# TOP.net
KiCad netlist of a schematic drawn in Altium Designer
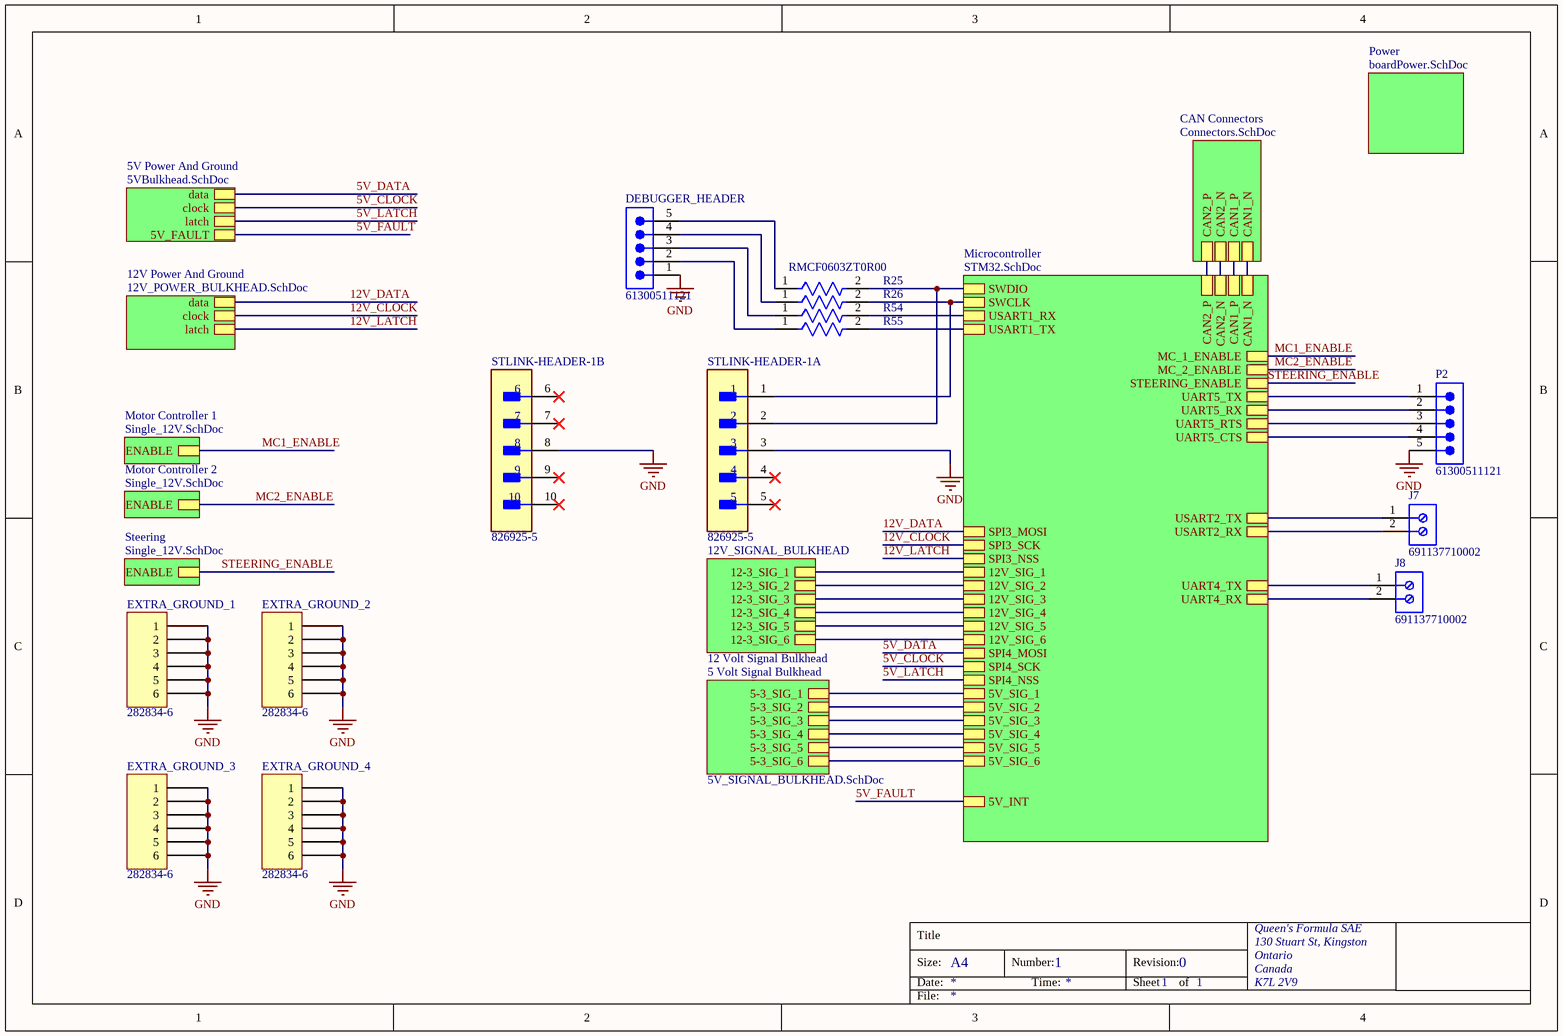
[diagram p0: TOP.SchDoc]

(export (version "E")
  (design (tool "Eeschema 10.0.6"))
  (components
    (comp (ref "DEBUGGER_HEADER")
      (value "61300511121")
      (footprint "61300511121")
      (libsource (lib "Altium Content Vault") (part "Header_Male_1R_05P"))
    )
    (comp (ref "EXTRA_GROUND_1")
      (value "282834-6")
      (footprint "TE 282834-6")
      (description "TERM BLK 6P SIDE ENT 2.54MM PCB")
      (fields (field (name "MANUFACTURER") "TE Connectivity AMP Connectors") (field (name "VOLTAGE") "150V"))
      (libsource (lib "Celestial Altium Library - altium_library") (part "6 Pin"))
    )
    (comp (ref "EXTRA_GROUND_2")
      (value "282834-6")
      (footprint "TE 282834-6")
      (description "TERM BLK 6P SIDE ENT 2.54MM PCB")
      (fields (field (name "MANUFACTURER") "TE Connectivity AMP Connectors") (field (name "VOLTAGE") "150V"))
      (libsource (lib "Celestial Altium Library - altium_library") (part "6 Pin"))
    )
    (comp (ref "EXTRA_GROUND_3")
      (value "282834-6")
      (footprint "TE 282834-6")
      (description "TERM BLK 6P SIDE ENT 2.54MM PCB")
      (fields (field (name "MANUFACTURER") "TE Connectivity AMP Connectors") (field (name "VOLTAGE") "150V"))
      (libsource (lib "Celestial Altium Library - altium_library") (part "6 Pin"))
    )
    (comp (ref "EXTRA_GROUND_4")
      (value "282834-6")
      (footprint "TE 282834-6")
      (description "TERM BLK 6P SIDE ENT 2.54MM PCB")
      (fields (field (name "MANUFACTURER") "TE Connectivity AMP Connectors") (field (name "VOLTAGE") "150V"))
      (libsource (lib "Celestial Altium Library - altium_library") (part "6 Pin"))
    )
    (comp (ref "J7")
      (value "691137710002")
      (footprint "691137710002")
      (libsource (lib "Altium Content Vault") (part "TBL - 1R - 02P - Screw"))
    )
    (comp (ref "J8")
      (value "691137710002")
      (footprint "691137710002")
      (libsource (lib "Altium Content Vault") (part "TBL - 1R - 02P - Screw"))
    )
    (comp (ref "P2")
      (value "61300511121")
      (footprint "61300511121")
      (libsource (lib "Altium Content Vault") (part "Header_Male_1R_05P"))
    )
    (comp (ref "R25")
      (value "RMCF0603ZT0R00")
      (footprint "FP-RMCF0603-MFG")
      (description "RES 0 OHM JUMPER 1/10W 0603")
      (fields
        (field (name "OCTOPART") "https://octopart.com/rmcf0603zt0r00-stackpole+electronics-19213618")
        (field (name "MANUFACTURER") "Stackpole")
      )
      (libsource (lib "Altium Content Vault") (part "1029c3af85768c4190bb7ad29bc67b5"))
    )
    (comp (ref "R26")
      (value "RMCF0603ZT0R00")
      (footprint "FP-RMCF0603-MFG")
      (description "RES 0 OHM JUMPER 1/10W 0603")
      (fields
        (field (name "OCTOPART") "https://octopart.com/rmcf0603zt0r00-stackpole+electronics-19213618")
        (field (name "MANUFACTURER") "Stackpole")
      )
      (libsource (lib "Altium Content Vault") (part "1029c3af85768c4190bb7ad29bc67b5"))
    )
    (comp (ref "R54")
      (value "RMCF0603ZT0R00")
      (footprint "FP-RMCF0603-MFG")
      (description "RES 0 OHM JUMPER 1/10W 0603")
      (fields
        (field (name "OCTOPART") "https://octopart.com/rmcf0603zt0r00-stackpole+electronics-19213618")
        (field (name "MANUFACTURER") "Stackpole")
      )
      (libsource (lib "Altium Content Vault") (part "1029c3af85768c4190bb7ad29bc67b5"))
    )
    (comp (ref "R55")
      (value "RMCF0603ZT0R00")
      (footprint "FP-RMCF0603-MFG")
      (description "RES 0 OHM JUMPER 1/10W 0603")
      (fields
        (field (name "OCTOPART") "https://octopart.com/rmcf0603zt0r00-stackpole+electronics-19213618")
        (field (name "MANUFACTURER") "Stackpole")
      )
      (libsource (lib "Altium Content Vault") (part "1029c3af85768c4190bb7ad29bc67b5"))
    )
    (comp (ref "STLINK-HEADER-1")
      (value "826925-5")
      (footprint "FP-826925-5-MFG")
      (description "CONN HEADER VERT 10POS 2.54MM")
      (fields
        (field (name "OCTOPART") "https://octopart.com/826925-5-te+connectivity-41836231")
        (field (name "MANUFACTURER") "TE Connectivity")
      )
      (libsource (lib "Altium Content Vault") (part "de255ff815dec4fe6d5caee7def00c9"))
    )
  )
  (nets
    (net (code "27") (name "/SWCLK") (class "Default")
      (node (ref "R26") (pin "2") (pinfunction "2_2") (pintype "passive"))
      (node (ref "STLINK-HEADER-1") (pin "1") (pinfunction "1_1") (pintype "passive"))
    )
    (net (code "28") (name "/SWDIO") (class "Default")
      (node (ref "R25") (pin "2") (pinfunction "2_2") (pintype "passive"))
      (node (ref "STLINK-HEADER-1") (pin "2") (pinfunction "2_2") (pintype "passive"))
    )
    (net (code "29") (name "/UART4_RX") (class "Default")
      (node (ref "J8") (pin "2") (pinfunction "2_2") (pintype "passive"))
    )
    (net (code "30") (name "/UART4_TX") (class "Default")
      (node (ref "J8") (pin "1") (pinfunction "1_1") (pintype "passive"))
    )
    (net (code "31") (name "/UART5_CTS") (class "Default")
      (node (ref "P2") (pin "4") (pinfunction "4_4") (pintype "passive"))
    )
    (net (code "32") (name "/UART5_RTS") (class "Default")
      (node (ref "P2") (pin "3") (pinfunction "3_3") (pintype "passive"))
    )
    (net (code "33") (name "/UART5_RX") (class "Default")
      (node (ref "P2") (pin "2") (pinfunction "2_2") (pintype "passive"))
    )
    (net (code "34") (name "/UART5_TX") (class "Default")
      (node (ref "P2") (pin "1") (pinfunction "1_1") (pintype "passive"))
    )
    (net (code "35") (name "/USART1_RX") (class "Default")
      (node (ref "R54") (pin "2") (pinfunction "2_2") (pintype "passive"))
    )
    (net (code "36") (name "/USART1_TX") (class "Default")
      (node (ref "R55") (pin "2") (pinfunction "2_2") (pintype "passive"))
    )
    (net (code "37") (name "/USART2_RX") (class "Default")
      (node (ref "J7") (pin "2") (pinfunction "2_2") (pintype "passive"))
    )
    (net (code "38") (name "/USART2_TX") (class "Default")
      (node (ref "J7") (pin "1") (pinfunction "1_1") (pintype "passive"))
    )
    (net (code "39") (name "GND") (class "Default")
      (node (ref "DEBUGGER_HEADER") (pin "1") (pinfunction "1_1") (pintype "passive"))
      (node (ref "EXTRA_GROUND_1") (pin "1") (pinfunction "1_1") (pintype "passive"))
      (node (ref "EXTRA_GROUND_1") (pin "2") (pinfunction "2_2") (pintype "passive"))
      (node (ref "EXTRA_GROUND_1") (pin "3") (pinfunction "3_3") (pintype "passive"))
      (node (ref "EXTRA_GROUND_1") (pin "4") (pinfunction "4_4") (pintype "passive"))
      (node (ref "EXTRA_GROUND_1") (pin "5") (pinfunction "5_5") (pintype "passive"))
      (node (ref "EXTRA_GROUND_1") (pin "6") (pinfunction "6_6") (pintype "passive"))
      (node (ref "EXTRA_GROUND_2") (pin "1") (pinfunction "1_1") (pintype "passive"))
      (node (ref "EXTRA_GROUND_2") (pin "2") (pinfunction "2_2") (pintype "passive"))
      (node (ref "EXTRA_GROUND_2") (pin "3") (pinfunction "3_3") (pintype "passive"))
      (node (ref "EXTRA_GROUND_2") (pin "4") (pinfunction "4_4") (pintype "passive"))
      (node (ref "EXTRA_GROUND_2") (pin "5") (pinfunction "5_5") (pintype "passive"))
      (node (ref "EXTRA_GROUND_2") (pin "6") (pinfunction "6_6") (pintype "passive"))
      (node (ref "EXTRA_GROUND_3") (pin "1") (pinfunction "1_1") (pintype "passive"))
      (node (ref "EXTRA_GROUND_3") (pin "2") (pinfunction "2_2") (pintype "passive"))
      (node (ref "EXTRA_GROUND_3") (pin "3") (pinfunction "3_3") (pintype "passive"))
      (node (ref "EXTRA_GROUND_3") (pin "4") (pinfunction "4_4") (pintype "passive"))
      (node (ref "EXTRA_GROUND_3") (pin "5") (pinfunction "5_5") (pintype "passive"))
      (node (ref "EXTRA_GROUND_3") (pin "6") (pinfunction "6_6") (pintype "passive"))
      (node (ref "EXTRA_GROUND_4") (pin "1") (pinfunction "1_1") (pintype "passive"))
      (node (ref "EXTRA_GROUND_4") (pin "2") (pinfunction "2_2") (pintype "passive"))
      (node (ref "EXTRA_GROUND_4") (pin "3") (pinfunction "3_3") (pintype "passive"))
      (node (ref "EXTRA_GROUND_4") (pin "4") (pinfunction "4_4") (pintype "passive"))
      (node (ref "EXTRA_GROUND_4") (pin "5") (pinfunction "5_5") (pintype "passive"))
      (node (ref "EXTRA_GROUND_4") (pin "6") (pinfunction "6_6") (pintype "passive"))
      (node (ref "P2") (pin "5") (pinfunction "5_5") (pintype "passive"))
      (node (ref "STLINK-HEADER-1") (pin "3") (pinfunction "3_3") (pintype "passive"))
      (node (ref "STLINK-HEADER-1") (pin "8") (pinfunction "8_8") (pintype "passive"))
    )
    (net (code "40") (name "Net-(DEBUGGER_HEADER-Pad2)") (class "Default")
      (node (ref "DEBUGGER_HEADER") (pin "2") (pinfunction "2_2") (pintype "passive"))
      (node (ref "R55") (pin "1") (pinfunction "1_1") (pintype "passive"))
    )
    (net (code "41") (name "Net-(DEBUGGER_HEADER-Pad3)") (class "Default")
      (node (ref "DEBUGGER_HEADER") (pin "3") (pinfunction "3_3") (pintype "passive"))
      (node (ref "R54") (pin "1") (pinfunction "1_1") (pintype "passive"))
    )
    (net (code "42") (name "Net-(DEBUGGER_HEADER-Pad4)") (class "Default")
      (node (ref "DEBUGGER_HEADER") (pin "4") (pinfunction "4_4") (pintype "passive"))
      (node (ref "R26") (pin "1") (pinfunction "1_1") (pintype "passive"))
    )
    (net (code "43") (name "Net-(DEBUGGER_HEADER-Pad5)") (class "Default")
      (node (ref "DEBUGGER_HEADER") (pin "5") (pinfunction "5_5") (pintype "passive"))
      (node (ref "R25") (pin "1") (pinfunction "1_1") (pintype "passive"))
    )
    (net (code "44") (name "unconnected-(STLINK-HEADER-1-Pad4)") (class "Default")
      (node (ref "STLINK-HEADER-1") (pin "4") (pinfunction "4_4") (pintype "passive+no_connect"))
    )
    (net (code "45") (name "unconnected-(STLINK-HEADER-1-Pad5)") (class "Default")
      (node (ref "STLINK-HEADER-1") (pin "5") (pinfunction "5_5") (pintype "passive+no_connect"))
    )
    (net (code "46") (name "unconnected-(STLINK-HEADER-1-Pad6)") (class "Default")
      (node (ref "STLINK-HEADER-1") (pin "6") (pinfunction "6_6") (pintype "passive+no_connect"))
    )
    (net (code "47") (name "unconnected-(STLINK-HEADER-1-Pad7)") (class "Default")
      (node (ref "STLINK-HEADER-1") (pin "7") (pinfunction "7_7") (pintype "passive+no_connect"))
    )
    (net (code "48") (name "unconnected-(STLINK-HEADER-1-Pad9)") (class "Default")
      (node (ref "STLINK-HEADER-1") (pin "9") (pinfunction "9_9") (pintype "passive+no_connect"))
    )
    (net (code "49") (name "unconnected-(STLINK-HEADER-1-Pad10)") (class "Default")
      (node (ref "STLINK-HEADER-1") (pin "10") (pinfunction "10_10") (pintype "passive+no_connect"))
    )
  )
)
